# main.net
KiCad netlist of a schematic drawn in EAGLE
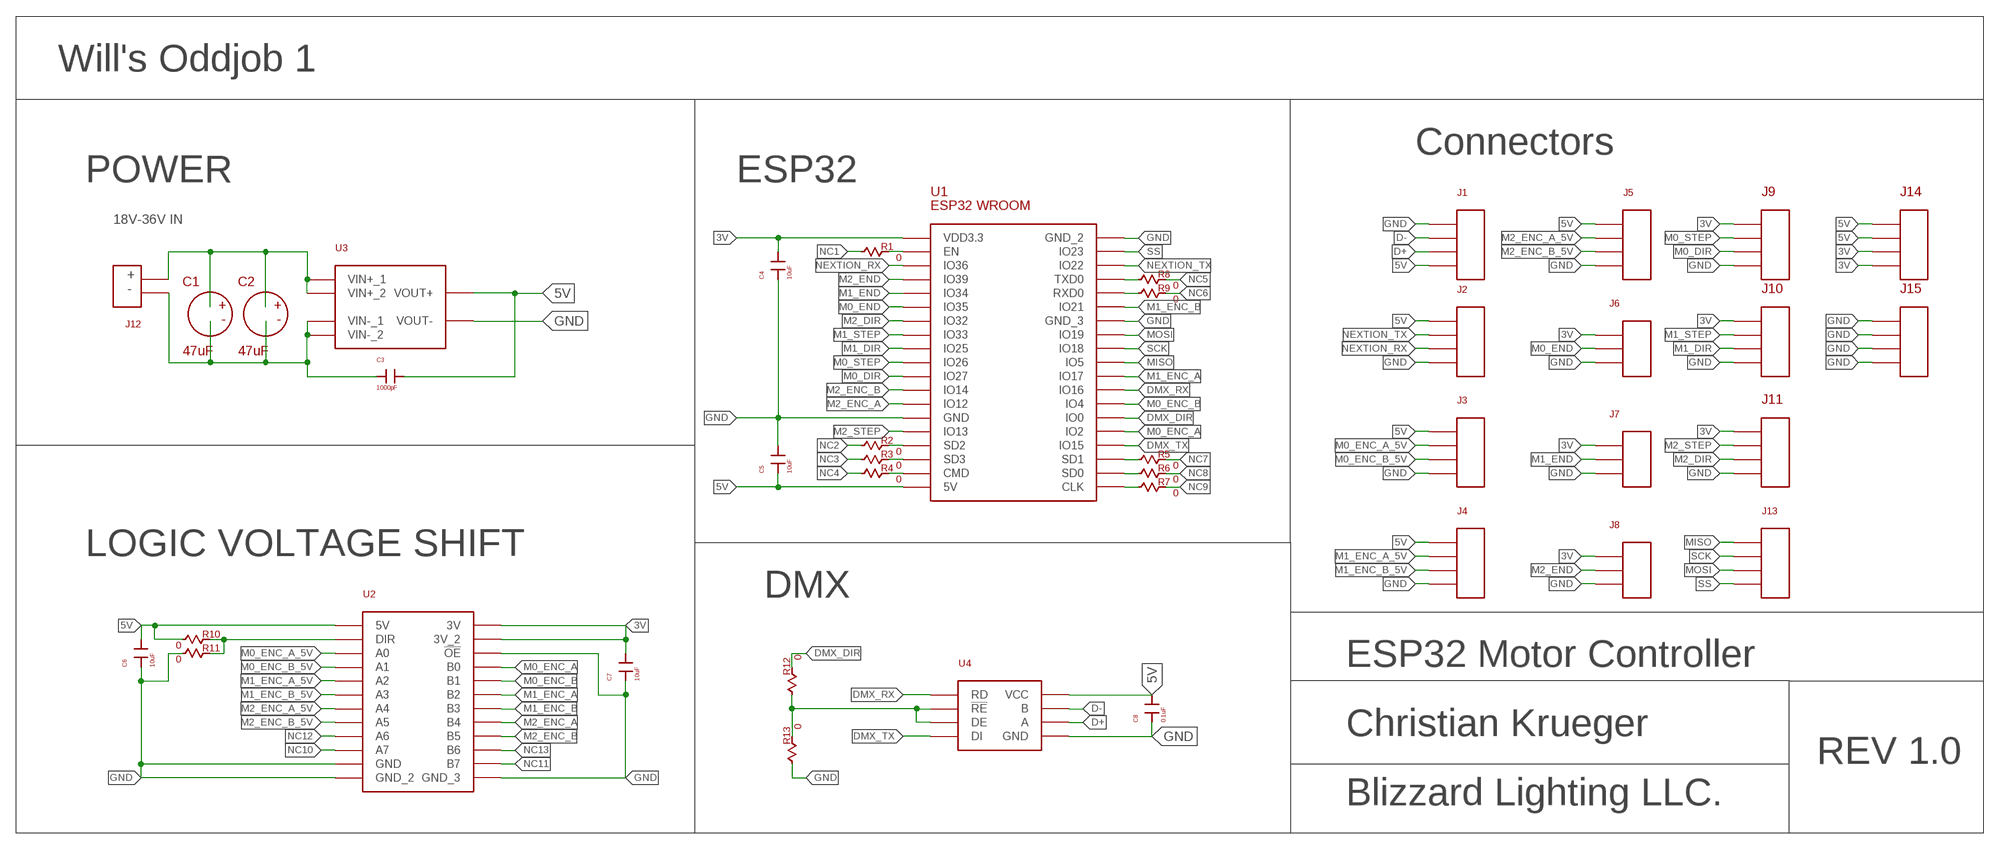
[diagram p0: schematic, sheet 1]

(export (version "E")
  (design (tool "Eeschema 10.0.6"))
  (components
    (comp (ref "C1")
      (value "47uF")
      (footprint "eagle-import:TH_CAP_PKG")
      (libsource (lib "eagle-import") (part "TH_CAP_DEV"))
    )
    (comp (ref "C2")
      (value "47uF")
      (footprint "eagle-import:TH_CAP_PKG")
      (libsource (lib "eagle-import") (part "TH_CAP_DEV"))
    )
    (comp (ref "C3")
      (value "1000pF")
      (footprint "eagle-import:1808_PKG")
      (libsource (lib "eagle-import") (part "1808_CAP_DEV"))
    )
    (comp (ref "C4")
      (value "10uF")
      (footprint "eagle-import:0805_PKG")
      (libsource (lib "eagle-import") (part "0805_CAP_DEV"))
    )
    (comp (ref "C5")
      (value "10uF")
      (footprint "eagle-import:0805_PKG")
      (libsource (lib "eagle-import") (part "0805_CAP_DEV"))
    )
    (comp (ref "C6")
      (value "10uF")
      (footprint "eagle-import:0805_PKG")
      (libsource (lib "eagle-import") (part "0805_CAP_DEV"))
    )
    (comp (ref "C7")
      (value "10uF")
      (footprint "eagle-import:0805_PKG")
      (libsource (lib "eagle-import") (part "0805_CAP_DEV"))
    )
    (comp (ref "C8")
      (value "0.1uF")
      (footprint "eagle-import:0805_PKG")
      (libsource (lib "eagle-import") (part "0805_CAP_DEV"))
    )
    (comp (ref "J1")
      (value "XH_4POS_DEV")
      (footprint "eagle-import:XH_4POS_PKG")
      (libsource (lib "eagle-import") (part "XH_4POS_DEV"))
    )
    (comp (ref "J2")
      (value "XH_4POS_DEV")
      (footprint "eagle-import:XH_4POS_PKG")
      (libsource (lib "eagle-import") (part "XH_4POS_DEV"))
    )
    (comp (ref "J3")
      (value "XH_4POS_DEV")
      (footprint "eagle-import:XH_4POS_PKG")
      (libsource (lib "eagle-import") (part "XH_4POS_DEV"))
    )
    (comp (ref "J4")
      (value "XH_4POS_DEV")
      (footprint "eagle-import:XH_4POS_PKG")
      (libsource (lib "eagle-import") (part "XH_4POS_DEV"))
    )
    (comp (ref "J5")
      (value "XH_4POS_DEV")
      (footprint "eagle-import:XH_4POS_PKG")
      (libsource (lib "eagle-import") (part "XH_4POS_DEV"))
    )
    (comp (ref "J6")
      (value "XH_3POS_DEV")
      (footprint "eagle-import:XH_3POS_PKG")
      (libsource (lib "eagle-import") (part "XH_3POS_DEV"))
    )
    (comp (ref "J7")
      (value "XH_3POS_DEV")
      (footprint "eagle-import:XH_3POS_PKG")
      (libsource (lib "eagle-import") (part "XH_3POS_DEV"))
    )
    (comp (ref "J8")
      (value "XH_3POS_DEV")
      (footprint "eagle-import:XH_3POS_PKG")
      (libsource (lib "eagle-import") (part "XH_3POS_DEV"))
    )
    (comp (ref "J9")
      (value "4_PIN_SCREW_3.5MM_DEV")
      (footprint "eagle-import:4_PIN_SCREW_3.5MM_PKG")
      (libsource (lib "eagle-import") (part "4_PIN_SCREW_3.5MM_DEV"))
    )
    (comp (ref "J10")
      (value "4_PIN_SCREW_3.5MM_DEV")
      (footprint "eagle-import:4_PIN_SCREW_3.5MM_PKG")
      (libsource (lib "eagle-import") (part "4_PIN_SCREW_3.5MM_DEV"))
    )
    (comp (ref "J11")
      (value "4_PIN_SCREW_3.5MM_DEV")
      (footprint "eagle-import:4_PIN_SCREW_3.5MM_PKG")
      (libsource (lib "eagle-import") (part "4_PIN_SCREW_3.5MM_DEV"))
    )
    (comp (ref "J12")
      (value "2_PIN_SCREW_3.5MM_DEV")
      (footprint "eagle-import:2_PIN_SCREW_3.5MM_PKG")
      (libsource (lib "eagle-import") (part "2_PIN_SCREW_3.5MM_DEV"))
    )
    (comp (ref "J13")
      (value "4_PIN_2.54MM_PKG")
      (footprint "eagle-import:4_PIN_2.54MM_PKG")
      (libsource (lib "eagle-import") (part "4_PIN_2.54MM_PKG"))
    )
    (comp (ref "J14")
      (value "4_PIN_SCREW_3.5MM_DEV")
      (footprint "eagle-import:4_PIN_SCREW_3.5MM_PKG")
      (libsource (lib "eagle-import") (part "4_PIN_SCREW_3.5MM_DEV"))
    )
    (comp (ref "J15")
      (value "4_PIN_SCREW_3.5MM_DEV")
      (footprint "eagle-import:4_PIN_SCREW_3.5MM_PKG")
      (libsource (lib "eagle-import") (part "4_PIN_SCREW_3.5MM_DEV"))
    )
    (comp (ref "R1")
      (value "0")
      (footprint "eagle-import:0805_PKG")
      (libsource (lib "eagle-import") (part "0805_RES_DEV"))
    )
    (comp (ref "R2")
      (value "0")
      (footprint "eagle-import:0805_PKG")
      (libsource (lib "eagle-import") (part "0805_RES_DEV"))
    )
    (comp (ref "R3")
      (value "0")
      (footprint "eagle-import:0805_PKG")
      (libsource (lib "eagle-import") (part "0805_RES_DEV"))
    )
    (comp (ref "R4")
      (value "0")
      (footprint "eagle-import:0805_PKG")
      (libsource (lib "eagle-import") (part "0805_RES_DEV"))
    )
    (comp (ref "R5")
      (value "0")
      (footprint "eagle-import:0805_PKG")
      (libsource (lib "eagle-import") (part "0805_RES_DEV"))
    )
    (comp (ref "R6")
      (value "0")
      (footprint "eagle-import:0805_PKG")
      (libsource (lib "eagle-import") (part "0805_RES_DEV"))
    )
    (comp (ref "R7")
      (value "0")
      (footprint "eagle-import:0805_PKG")
      (libsource (lib "eagle-import") (part "0805_RES_DEV"))
    )
    (comp (ref "R8")
      (value "0")
      (footprint "eagle-import:0805_PKG")
      (libsource (lib "eagle-import") (part "0805_RES_DEV"))
    )
    (comp (ref "R9")
      (value "0")
      (footprint "eagle-import:0805_PKG")
      (libsource (lib "eagle-import") (part "0805_RES_DEV"))
    )
    (comp (ref "R10")
      (value "0")
      (footprint "eagle-import:0805_PKG")
      (libsource (lib "eagle-import") (part "0805_RES_DEV"))
    )
    (comp (ref "R11")
      (value "0")
      (footprint "eagle-import:0805_PKG")
      (libsource (lib "eagle-import") (part "0805_RES_DEV"))
    )
    (comp (ref "R12")
      (value "0")
      (footprint "eagle-import:0805_PKG")
      (libsource (lib "eagle-import") (part "0805_RES_DEV"))
    )
    (comp (ref "R13")
      (value "0")
      (footprint "eagle-import:0805_PKG")
      (libsource (lib "eagle-import") (part "0805_RES_DEV"))
    )
    (comp (ref "U1")
      (value "ESP32_WROOM_BREAKOUT_DEV")
      (footprint "eagle-import:ESP_WROOM_BREAKOUT_PKG")
      (libsource (lib "eagle-import") (part "ESP32_WROOM_BREAKOUT_DEV"))
    )
    (comp (ref "U2")
      (value "8_CHANNEL_LEVEL_SHIFTER")
      (footprint "eagle-import:8_LEVEL_SHIFTER_PKG")
      (libsource (lib "eagle-import") (part "8_CHANNEL_LEVEL_SHIFTER"))
    )
    (comp (ref "U3")
      (value "5V_SWITCHING_POWER_DEV")
      (footprint "eagle-import:5V_SWITCHING_POWER_PKG")
      (libsource (lib "eagle-import") (part "5V_SWITCHING_POWER_DEV"))
    )
    (comp (ref "U4")
      (value "MAX_485_DEV")
      (footprint "eagle-import:MAX_485_PKG")
      (libsource (lib "eagle-import") (part "MAX_485_DEV"))
    )
  )
  (nets
    (net (code "1") (name "3V") (class "Default")
      (node (ref "C4") (pin "P$2") (pinfunction "P$2_P$2") (pintype "bidirectional"))
      (node (ref "C7") (pin "P$2") (pinfunction "P$2_P$2") (pintype "bidirectional"))
      (node (ref "J10") (pin "1") (pinfunction "P$1_1") (pintype "bidirectional"))
      (node (ref "J11") (pin "1") (pinfunction "P$1_1") (pintype "bidirectional"))
      (node (ref "J14") (pin "3") (pinfunction "P$3_3") (pintype "bidirectional"))
      (node (ref "J14") (pin "4") (pinfunction "P$4_4") (pintype "bidirectional"))
      (node (ref "J6") (pin "P$1") (pinfunction "1_P$1") (pintype "bidirectional"))
      (node (ref "J7") (pin "P$1") (pinfunction "1_P$1") (pintype "bidirectional"))
      (node (ref "J8") (pin "P$1") (pinfunction "1_P$1") (pintype "bidirectional"))
      (node (ref "J9") (pin "1") (pinfunction "P$1_1") (pintype "bidirectional"))
      (node (ref "U1") (pin "VDD3.3") (pinfunction "VDD3.3_VDD3.3") (pintype "bidirectional"))
      (node (ref "U2") (pin "3V") (pinfunction "3V_3V") (pintype "bidirectional"))
      (node (ref "U2") (pin "3V_2") (pinfunction "3V_2_3V_2") (pintype "bidirectional"))
    )
    (net (code "2") (name "5V") (class "Default")
      (node (ref "C3") (pin "P$2") (pinfunction "P$2_P$2") (pintype "bidirectional"))
      (node (ref "C5") (pin "P$1") (pinfunction "P$1_P$1") (pintype "bidirectional"))
      (node (ref "C6") (pin "P$2") (pinfunction "P$2_P$2") (pintype "bidirectional"))
      (node (ref "C8") (pin "P$2") (pinfunction "P$2_P$2") (pintype "bidirectional"))
      (node (ref "J1") (pin "P$4") (pinfunction "P$4_P$4") (pintype "bidirectional"))
      (node (ref "J14") (pin "1") (pinfunction "P$1_1") (pintype "bidirectional"))
      (node (ref "J14") (pin "2") (pinfunction "P$2_2") (pintype "bidirectional"))
      (node (ref "J2") (pin "P$1") (pinfunction "P$1_P$1") (pintype "bidirectional"))
      (node (ref "J3") (pin "P$1") (pinfunction "P$1_P$1") (pintype "bidirectional"))
      (node (ref "J4") (pin "P$1") (pinfunction "P$1_P$1") (pintype "bidirectional"))
      (node (ref "J5") (pin "P$1") (pinfunction "P$1_P$1") (pintype "bidirectional"))
      (node (ref "R10") (pin "P$1") (pinfunction "P$1_P$1") (pintype "bidirectional"))
      (node (ref "U1") (pin "5V") (pinfunction "5V_5V") (pintype "bidirectional"))
      (node (ref "U2") (pin "5V") (pinfunction "5V_5V") (pintype "bidirectional"))
      (node (ref "U3") (pin "VOUT+") (pinfunction "VOUT+_VOUT+") (pintype "bidirectional"))
      (node (ref "U4") (pin "P$8") (pinfunction "VCC_P$8") (pintype "bidirectional"))
    )
    (net (code "3") (name "D+") (class "Default")
      (node (ref "J1") (pin "P$3") (pinfunction "P$3_P$3") (pintype "bidirectional"))
      (node (ref "U4") (pin "P$6") (pinfunction "A_P$6") (pintype "bidirectional"))
    )
    (net (code "4") (name "D-") (class "Default")
      (node (ref "J1") (pin "P$2") (pinfunction "P$2_P$2") (pintype "bidirectional"))
      (node (ref "U4") (pin "P$7") (pinfunction "B_P$7") (pintype "bidirectional"))
    )
    (net (code "5") (name "DMX_DIR") (class "Default")
      (node (ref "R12") (pin "P$2") (pinfunction "P$2_P$2") (pintype "bidirectional"))
      (node (ref "U1") (pin "IO0") (pinfunction "IO0_IO0") (pintype "bidirectional"))
    )
    (net (code "6") (name "DMX_RX") (class "Default")
      (node (ref "U1") (pin "IO16") (pinfunction "IO16_IO16") (pintype "bidirectional"))
      (node (ref "U4") (pin "P$1") (pinfunction "RD_P$1") (pintype "bidirectional"))
    )
    (net (code "7") (name "DMX_TX") (class "Default")
      (node (ref "U1") (pin "IO15") (pinfunction "IO15_IO15") (pintype "bidirectional"))
      (node (ref "U4") (pin "P$4") (pinfunction "DI_P$4") (pintype "bidirectional"))
    )
    (net (code "8") (name "GND") (class "Default")
      (node (ref "C4") (pin "P$1") (pinfunction "P$1_P$1") (pintype "bidirectional"))
      (node (ref "C5") (pin "P$2") (pinfunction "P$2_P$2") (pintype "bidirectional"))
      (node (ref "C6") (pin "P$1") (pinfunction "P$1_P$1") (pintype "bidirectional"))
      (node (ref "C7") (pin "P$1") (pinfunction "P$1_P$1") (pintype "bidirectional"))
      (node (ref "C8") (pin "P$1") (pinfunction "P$1_P$1") (pintype "bidirectional"))
      (node (ref "J1") (pin "P$1") (pinfunction "P$1_P$1") (pintype "bidirectional"))
      (node (ref "J10") (pin "4") (pinfunction "P$4_4") (pintype "bidirectional"))
      (node (ref "J11") (pin "4") (pinfunction "P$4_4") (pintype "bidirectional"))
      (node (ref "J15") (pin "1") (pinfunction "P$1_1") (pintype "bidirectional"))
      (node (ref "J15") (pin "2") (pinfunction "P$2_2") (pintype "bidirectional"))
      (node (ref "J15") (pin "3") (pinfunction "P$3_3") (pintype "bidirectional"))
      (node (ref "J15") (pin "4") (pinfunction "P$4_4") (pintype "bidirectional"))
      (node (ref "J2") (pin "P$4") (pinfunction "P$4_P$4") (pintype "bidirectional"))
      (node (ref "J3") (pin "P$4") (pinfunction "P$4_P$4") (pintype "bidirectional"))
      (node (ref "J4") (pin "P$4") (pinfunction "P$4_P$4") (pintype "bidirectional"))
      (node (ref "J5") (pin "P$4") (pinfunction "P$4_P$4") (pintype "bidirectional"))
      (node (ref "J6") (pin "P$3") (pinfunction "3_P$3") (pintype "bidirectional"))
      (node (ref "J7") (pin "P$3") (pinfunction "3_P$3") (pintype "bidirectional"))
      (node (ref "J8") (pin "P$3") (pinfunction "3_P$3") (pintype "bidirectional"))
      (node (ref "J9") (pin "4") (pinfunction "P$4_4") (pintype "bidirectional"))
      (node (ref "R11") (pin "P$1") (pinfunction "P$1_P$1") (pintype "bidirectional"))
      (node (ref "R13") (pin "P$1") (pinfunction "P$1_P$1") (pintype "bidirectional"))
      (node (ref "U1") (pin "GND") (pinfunction "GND_GND") (pintype "bidirectional"))
      (node (ref "U1") (pin "GND_2") (pinfunction "GND_2_GND_2") (pintype "bidirectional"))
      (node (ref "U1") (pin "GND_3") (pinfunction "GND_3_GND_3") (pintype "bidirectional"))
      (node (ref "U2") (pin "!OE") (pinfunction "~{OE}_!OE") (pintype "bidirectional"))
      (node (ref "U2") (pin "GND") (pinfunction "GND_GND") (pintype "bidirectional"))
      (node (ref "U2") (pin "GND_2") (pinfunction "GND_2_GND_2") (pintype "bidirectional"))
      (node (ref "U2") (pin "GND_3") (pinfunction "GND_3_GND_3") (pintype "bidirectional"))
      (node (ref "U3") (pin "VOUT-") (pinfunction "VOUT-_VOUT-") (pintype "bidirectional"))
      (node (ref "U4") (pin "P$5") (pinfunction "GND_P$5") (pintype "bidirectional"))
    )
    (net (code "9") (name "M0_DIR") (class "Default")
      (node (ref "J9") (pin "3") (pinfunction "P$3_3") (pintype "bidirectional"))
      (node (ref "U1") (pin "IO27") (pinfunction "IO27_IO27") (pintype "bidirectional"))
    )
    (net (code "10") (name "M0_ENC_A") (class "Default")
      (node (ref "U1") (pin "IO2") (pinfunction "IO2_IO2") (pintype "bidirectional"))
      (node (ref "U2") (pin "B0") (pinfunction "B0_B0") (pintype "bidirectional"))
    )
    (net (code "11") (name "M0_ENC_A_5V") (class "Default")
      (node (ref "J3") (pin "P$2") (pinfunction "P$2_P$2") (pintype "bidirectional"))
      (node (ref "U2") (pin "A0") (pinfunction "A0_A0") (pintype "bidirectional"))
    )
    (net (code "12") (name "M0_ENC_B") (class "Default")
      (node (ref "U1") (pin "IO4") (pinfunction "IO4_IO4") (pintype "bidirectional"))
      (node (ref "U2") (pin "B1") (pinfunction "B1_B1") (pintype "bidirectional"))
    )
    (net (code "13") (name "M0_ENC_B_5V") (class "Default")
      (node (ref "J3") (pin "P$3") (pinfunction "P$3_P$3") (pintype "bidirectional"))
      (node (ref "U2") (pin "A1") (pinfunction "A1_A1") (pintype "bidirectional"))
    )
    (net (code "14") (name "M0_END") (class "Default")
      (node (ref "J6") (pin "P$2") (pinfunction "2_P$2") (pintype "bidirectional"))
      (node (ref "U1") (pin "IO35") (pinfunction "IO35_IO35") (pintype "bidirectional"))
    )
    (net (code "15") (name "M0_STEP") (class "Default")
      (node (ref "J9") (pin "2") (pinfunction "P$2_2") (pintype "bidirectional"))
      (node (ref "U1") (pin "IO26") (pinfunction "IO26_IO26") (pintype "bidirectional"))
    )
    (net (code "16") (name "M1_DIR") (class "Default")
      (node (ref "J10") (pin "3") (pinfunction "P$3_3") (pintype "bidirectional"))
      (node (ref "U1") (pin "IO25") (pinfunction "IO25_IO25") (pintype "bidirectional"))
    )
    (net (code "17") (name "M1_ENC_A") (class "Default")
      (node (ref "U1") (pin "IO17") (pinfunction "IO17_IO17") (pintype "bidirectional"))
      (node (ref "U2") (pin "B2") (pinfunction "B2_B2") (pintype "bidirectional"))
    )
    (net (code "18") (name "M1_ENC_A_5V") (class "Default")
      (node (ref "J4") (pin "P$2") (pinfunction "P$2_P$2") (pintype "bidirectional"))
      (node (ref "U2") (pin "A2") (pinfunction "A2_A2") (pintype "bidirectional"))
    )
    (net (code "19") (name "M1_ENC_B") (class "Default")
      (node (ref "U1") (pin "IO21") (pinfunction "IO21_IO21") (pintype "bidirectional"))
      (node (ref "U2") (pin "B3") (pinfunction "B3_B3") (pintype "bidirectional"))
    )
    (net (code "20") (name "M1_ENC_B_5V") (class "Default")
      (node (ref "J4") (pin "P$3") (pinfunction "P$3_P$3") (pintype "bidirectional"))
      (node (ref "U2") (pin "A3") (pinfunction "A3_A3") (pintype "bidirectional"))
    )
    (net (code "21") (name "M1_END") (class "Default")
      (node (ref "J7") (pin "P$2") (pinfunction "2_P$2") (pintype "bidirectional"))
      (node (ref "U1") (pin "IO34") (pinfunction "IO34_IO34") (pintype "bidirectional"))
    )
    (net (code "22") (name "M1_STEP") (class "Default")
      (node (ref "J10") (pin "2") (pinfunction "P$2_2") (pintype "bidirectional"))
      (node (ref "U1") (pin "IO33") (pinfunction "IO33_IO33") (pintype "bidirectional"))
    )
    (net (code "23") (name "M2_DIR") (class "Default")
      (node (ref "J11") (pin "3") (pinfunction "P$3_3") (pintype "bidirectional"))
      (node (ref "U1") (pin "IO32") (pinfunction "IO32_IO32") (pintype "bidirectional"))
    )
    (net (code "24") (name "M2_ENC_A") (class "Default")
      (node (ref "U1") (pin "IO12") (pinfunction "IO12_IO12") (pintype "bidirectional"))
      (node (ref "U2") (pin "B4") (pinfunction "B4_B4") (pintype "bidirectional"))
    )
    (net (code "25") (name "M2_ENC_A_5V") (class "Default")
      (node (ref "J5") (pin "P$2") (pinfunction "P$2_P$2") (pintype "bidirectional"))
      (node (ref "U2") (pin "A4") (pinfunction "A4_A4") (pintype "bidirectional"))
    )
    (net (code "26") (name "M2_ENC_B") (class "Default")
      (node (ref "U1") (pin "IO14") (pinfunction "IO14_IO14") (pintype "bidirectional"))
      (node (ref "U2") (pin "B5") (pinfunction "B5_B5") (pintype "bidirectional"))
    )
    (net (code "27") (name "M2_ENC_B_5V") (class "Default")
      (node (ref "J5") (pin "P$3") (pinfunction "P$3_P$3") (pintype "bidirectional"))
      (node (ref "U2") (pin "A5") (pinfunction "A5_A5") (pintype "bidirectional"))
    )
    (net (code "28") (name "M2_END") (class "Default")
      (node (ref "J8") (pin "P$2") (pinfunction "2_P$2") (pintype "bidirectional"))
      (node (ref "U1") (pin "IO39") (pinfunction "IO39_IO39") (pintype "bidirectional"))
    )
    (net (code "29") (name "M2_STEP") (class "Default")
      (node (ref "J11") (pin "2") (pinfunction "P$2_2") (pintype "bidirectional"))
      (node (ref "U1") (pin "IO13") (pinfunction "IO13_IO13") (pintype "bidirectional"))
    )
    (net (code "30") (name "MISO") (class "Default")
      (node (ref "J13") (pin "1") (pinfunction "1_1") (pintype "bidirectional"))
      (node (ref "U1") (pin "IO5") (pinfunction "IO5_IO5") (pintype "bidirectional"))
    )
    (net (code "31") (name "MOSI") (class "Default")
      (node (ref "J13") (pin "3") (pinfunction "3_3") (pintype "bidirectional"))
      (node (ref "U1") (pin "IO19") (pinfunction "IO19_IO19") (pintype "bidirectional"))
    )
    (net (code "32") (name "NC1") (class "Default")
      (node (ref "R1") (pin "P$1") (pinfunction "P$1_P$1") (pintype "bidirectional"))
    )
    (net (code "33") (name "NC2") (class "Default")
      (node (ref "R2") (pin "P$1") (pinfunction "P$1_P$1") (pintype "bidirectional"))
    )
    (net (code "34") (name "NC3") (class "Default")
      (node (ref "R3") (pin "P$1") (pinfunction "P$1_P$1") (pintype "bidirectional"))
    )
    (net (code "35") (name "NC4") (class "Default")
      (node (ref "R4") (pin "P$1") (pinfunction "P$1_P$1") (pintype "bidirectional"))
    )
    (net (code "36") (name "NC5") (class "Default")
      (node (ref "R8") (pin "P$2") (pinfunction "P$2_P$2") (pintype "bidirectional"))
    )
    (net (code "37") (name "NC6") (class "Default")
      (node (ref "R9") (pin "P$2") (pinfunction "P$2_P$2") (pintype "bidirectional"))
    )
    (net (code "38") (name "NC7") (class "Default")
      (node (ref "R5") (pin "P$2") (pinfunction "P$2_P$2") (pintype "bidirectional"))
    )
    (net (code "39") (name "NC8") (class "Default")
      (node (ref "R6") (pin "P$2") (pinfunction "P$2_P$2") (pintype "bidirectional"))
    )
    (net (code "40") (name "NC9") (class "Default")
      (node (ref "R7") (pin "P$2") (pinfunction "P$2_P$2") (pintype "bidirectional"))
    )
    (net (code "41") (name "NC10") (class "Default")
      (node (ref "U2") (pin "A7") (pinfunction "A7_A7") (pintype "bidirectional"))
    )
    (net (code "42") (name "NC11") (class "Default")
      (node (ref "U2") (pin "B7") (pinfunction "B7_B7") (pintype "bidirectional"))
    )
    (net (code "43") (name "NC12") (class "Default")
      (node (ref "U2") (pin "A6") (pinfunction "A6_A6") (pintype "bidirectional"))
    )
    (net (code "44") (name "NC13") (class "Default")
      (node (ref "U2") (pin "B6") (pinfunction "B6_B6") (pintype "bidirectional"))
    )
    (net (code "45") (name "NEXTION_RX") (class "Default")
      (node (ref "J2") (pin "P$3") (pinfunction "P$3_P$3") (pintype "bidirectional"))
      (node (ref "U1") (pin "IO36") (pinfunction "IO36_IO36") (pintype "bidirectional"))
    )
    (net (code "46") (name "NEXTION_TX") (class "Default")
      (node (ref "J2") (pin "P$2") (pinfunction "P$2_P$2") (pintype "bidirectional"))
      (node (ref "U1") (pin "IO22") (pinfunction "IO22_IO22") (pintype "bidirectional"))
    )
    (net (code "47") (name "Net-(J12-1)") (class "Default")
      (node (ref "C1") (pin "P$2") (pinfunction "P$2_P$2") (pintype "bidirectional"))
      (node (ref "C2") (pin "P$2") (pinfunction "P$2_P$2") (pintype "bidirectional"))
      (node (ref "C3") (pin "P$1") (pinfunction "P$1_P$1") (pintype "bidirectional"))
      (node (ref "J12") (pin "P$1") (pinfunction "1_P$1") (pintype "bidirectional"))
      (node (ref "U3") (pin "VIN-_1") (pinfunction "VIN-_1_VIN-_1") (pintype "bidirectional"))
      (node (ref "U3") (pin "VIN-_2") (pinfunction "VIN-_2_VIN-_2") (pintype "bidirectional"))
    )
    (net (code "48") (name "Net-(J12-2)") (class "Default")
      (node (ref "C1") (pin "P$1") (pinfunction "P$1_P$1") (pintype "bidirectional"))
      (node (ref "C2") (pin "P$1") (pinfunction "P$1_P$1") (pintype "bidirectional"))
      (node (ref "J12") (pin "P$2") (pinfunction "2_P$2") (pintype "bidirectional"))
      (node (ref "U3") (pin "VIN+_1") (pinfunction "VIN+_1_VIN+_1") (pintype "bidirectional"))
      (node (ref "U3") (pin "VIN+_2") (pinfunction "VIN+_2_VIN+_2") (pintype "bidirectional"))
    )
    (net (code "49") (name "Net-(R1-PadP$2)") (class "Default")
      (node (ref "R1") (pin "P$2") (pinfunction "P$2_P$2") (pintype "bidirectional"))
      (node (ref "U1") (pin "EN") (pinfunction "EN_EN") (pintype "bidirectional"))
    )
    (net (code "50") (name "Net-(R2-PadP$2)") (class "Default")
      (node (ref "R2") (pin "P$2") (pinfunction "P$2_P$2") (pintype "bidirectional"))
      (node (ref "U1") (pin "SD2") (pinfunction "SD2_SD2") (pintype "bidirectional"))
    )
    (net (code "51") (name "Net-(R3-PadP$2)") (class "Default")
      (node (ref "R3") (pin "P$2") (pinfunction "P$2_P$2") (pintype "bidirectional"))
      (node (ref "U1") (pin "SD3") (pinfunction "SD3_SD3") (pintype "bidirectional"))
    )
    (net (code "52") (name "Net-(R4-PadP$2)") (class "Default")
      (node (ref "R4") (pin "P$2") (pinfunction "P$2_P$2") (pintype "bidirectional"))
      (node (ref "U1") (pin "CMD") (pinfunction "CMD_CMD") (pintype "bidirectional"))
    )
    (net (code "53") (name "Net-(R5-PadP$1)") (class "Default")
      (node (ref "R5") (pin "P$1") (pinfunction "P$1_P$1") (pintype "bidirectional"))
      (node (ref "U1") (pin "SD1") (pinfunction "SD1_SD1") (pintype "bidirectional"))
    )
    (net (code "54") (name "Net-(R6-PadP$1)") (class "Default")
      (node (ref "R6") (pin "P$1") (pinfunction "P$1_P$1") (pintype "bidirectional"))
      (node (ref "U1") (pin "SD0") (pinfunction "SD0_SD0") (pintype "bidirectional"))
    )
    (net (code "55") (name "Net-(R7-PadP$1)") (class "Default")
      (node (ref "R7") (pin "P$1") (pinfunction "P$1_P$1") (pintype "bidirectional"))
      (node (ref "U1") (pin "CLK") (pinfunction "CLK_CLK") (pintype "bidirectional"))
    )
    (net (code "56") (name "Net-(R8-PadP$1)") (class "Default")
      (node (ref "R8") (pin "P$1") (pinfunction "P$1_P$1") (pintype "bidirectional"))
      (node (ref "U1") (pin "TXD0") (pinfunction "TXD0_TXD0") (pintype "bidirectional"))
    )
    (net (code "57") (name "Net-(R9-PadP$1)") (class "Default")
      (node (ref "R9") (pin "P$1") (pinfunction "P$1_P$1") (pintype "bidirectional"))
      (node (ref "U1") (pin "RXD0") (pinfunction "RXD0_RXD0") (pintype "bidirectional"))
    )
    (net (code "58") (name "Net-(R10-PadP$2)") (class "Default")
      (node (ref "R10") (pin "P$2") (pinfunction "P$2_P$2") (pintype "bidirectional"))
      (node (ref "R11") (pin "P$2") (pinfunction "P$2_P$2") (pintype "bidirectional"))
      (node (ref "U2") (pin "DIR") (pinfunction "DIR_DIR") (pintype "bidirectional"))
    )
    (net (code "59") (name "Net-(U4-DE)") (class "Default")
      (node (ref "R12") (pin "P$1") (pinfunction "P$1_P$1") (pintype "bidirectional"))
      (node (ref "R13") (pin "P$2") (pinfunction "P$2_P$2") (pintype "bidirectional"))
      (node (ref "U4") (pin "P$2") (pinfunction "~{RE}_P$2") (pintype "bidirectional"))
      (node (ref "U4") (pin "P$3") (pinfunction "DE_P$3") (pintype "bidirectional"))
    )
    (net (code "60") (name "SCK") (class "Default")
      (node (ref "J13") (pin "2") (pinfunction "2_2") (pintype "bidirectional"))
      (node (ref "U1") (pin "IO18") (pinfunction "IO18_IO18") (pintype "bidirectional"))
    )
    (net (code "61") (name "SS") (class "Default")
      (node (ref "J13") (pin "4") (pinfunction "4_4") (pintype "bidirectional"))
      (node (ref "U1") (pin "IO23") (pinfunction "IO23_IO23") (pintype "bidirectional"))
    )
  )
)
